# PWU.net
KiCad netlist of a schematic drawn in Altium Designer
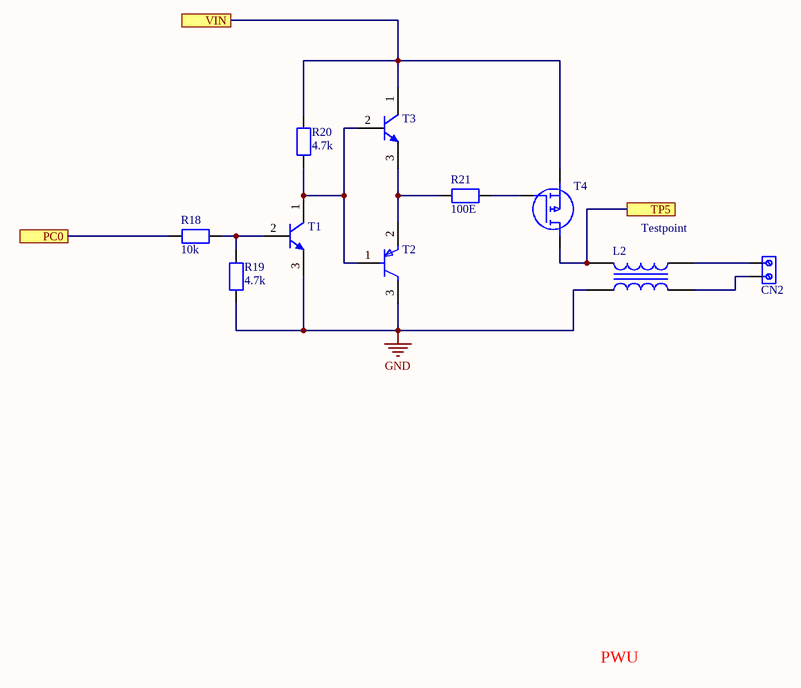
[diagram p0: PWU.SchDoc]

(export (version "E")
  (design (tool "Eeschema 10.0.6"))
  (components
    (comp (ref "CN2")
      (value "connecters 2pins")
      (footprint "conncecto 2 pins")
      (description "printkroonsteen 5,08 mm,")
      (libsource (lib "myOwnLib") (part "pins"))
    )
    (comp (ref "L2")
      (value "CM2545X171R-10")
      (footprint "LIRD-CM2545X171R-10_V")
      (description "Data Line Filter, 2 Function(s), 10A, 4 Pin(s)")
      (fields (field (name "MANUFACTURER") "Laird"))
      (libsource (lib "myOwnLib") (part "CM2545X171R-10"))
    )
    (comp (ref "R18")
      (value "10k")
      (footprint "RES_0805")
      (description "SMD size 0805 Generic.")
      (libsource (lib "myOwnLib") (part "RES_0805"))
    )
    (comp (ref "R19")
      (value "4.7k")
      (footprint "RES_0805")
      (description "SMD size 0805 Generic.")
      (libsource (lib "myOwnLib") (part "RES_0805"))
    )
    (comp (ref "R20")
      (value "4.7k")
      (footprint "RES_0805")
      (description "SMD size 0805 Generic.")
      (libsource (lib "myOwnLib") (part "RES_0805"))
    )
    (comp (ref "R21")
      (value "100E")
      (footprint "RES_0805")
      (description "SMD size 0805 Generic.")
      (libsource (lib "myOwnLib") (part "RES_0805"))
    )
    (comp (ref "T1")
      (value "BC547CG")
      (footprint "ONSC-TO-92-3-29-11")
      (description "Small Signal Bipolar Transistor, 0.1A I(C), 45V V(BR)CEO, 1-Element, NPN, Silicon, TO-92")
      (fields (field (name "MANUFACTURER") "ON Semiconductor"))
      (libsource (lib "myOwnLib") (part "BC547CG"))
    )
    (comp (ref "T2")
      (value "BCV26")
      (footprint "FP-318-IPC_C")
      (description "Small Signal Bipolar Transistor, 1.2A I(C), 30V V(BR)CEO, 1-Element, PNP, Silicon")
      (fields (field (name "MANUFACTURER") "ON Semiconductor / Fairchild"))
      (libsource (lib "myOwnLib") (part "BCV26"))
    )
    (comp (ref "T3")
      (value "BC547CG")
      (footprint "ONSC-TO-92-3-29-11")
      (description "Small Signal Bipolar Transistor, 0.1A I(C), 45V V(BR)CEO, 1-Element, NPN, Silicon, TO-92")
      (fields (field (name "MANUFACTURER") "ON Semiconductor"))
      (libsource (lib "myOwnLib") (part "BC547CG"))
    )
    (comp (ref "T4")
      (value "Mosfet")
      (footprint "TO254P469X1042X1967-3P")
      (description "Mosfet Transistor, IRF9Z34NPBF, generic.")
      (libsource (lib "myOwnLib") (part "Mosfet"))
    )
  )
  (nets
    (net (code "1") (name "/PC0") (class "Default") (node (ref "R18") (pin "1") (pintype "passive")))
    (net (code "2") (name "/TP5") (class "Default")
      (node (ref "L2") (pin "1") (pinfunction "1_1") (pintype "passive"))
      (node (ref "T4") (pin "3") (pinfunction "D_3") (pintype "passive"))
    )
    (net (code "3") (name "/VIN") (class "Default")
      (node (ref "R20") (pin "2") (pintype "passive"))
      (node (ref "T3") (pin "1") (pinfunction "C_1") (pintype "passive"))
      (node (ref "T4") (pin "2") (pinfunction "S_2") (pintype "passive"))
    )
    (net (code "4") (name "GND") (class "Default")
      (node (ref "L2") (pin "2") (pinfunction "2_2") (pintype "passive"))
      (node (ref "R19") (pin "1") (pintype "passive"))
      (node (ref "T1") (pin "3") (pinfunction "E_3") (pintype "passive"))
      (node (ref "T2") (pin "3") (pinfunction "C_3") (pintype "passive"))
    )
    (net (code "5") (name "Net-(CN2-Pad1)") (class "Default")
      (node (ref "CN2") (pin "1") (pinfunction "1_1") (pintype "passive"))
      (node (ref "L2") (pin "4") (pinfunction "4_4") (pintype "passive"))
    )
    (net (code "6") (name "Net-(CN2-Pad2)") (class "Default")
      (node (ref "CN2") (pin "2") (pinfunction "2_2") (pintype "passive"))
      (node (ref "L2") (pin "3") (pinfunction "3_3") (pintype "passive"))
    )
    (net (code "7") (name "Net-(T1-B)") (class "Default")
      (node (ref "R18") (pin "2") (pintype "passive"))
      (node (ref "R19") (pin "2") (pintype "passive"))
      (node (ref "T1") (pin "2") (pinfunction "B_2") (pintype "passive"))
    )
    (net (code "8") (name "Net-(T1-C)") (class "Default")
      (node (ref "R20") (pin "1") (pintype "passive"))
      (node (ref "T1") (pin "1") (pinfunction "C_1") (pintype "passive"))
      (node (ref "T2") (pin "1") (pinfunction "B_1") (pintype "passive"))
      (node (ref "T3") (pin "2") (pinfunction "B_2") (pintype "passive"))
    )
    (net (code "9") (name "Net-(T2-E)") (class "Default")
      (node (ref "R21") (pin "1") (pintype "passive"))
      (node (ref "T2") (pin "2") (pinfunction "E_2") (pintype "passive"))
      (node (ref "T3") (pin "3") (pinfunction "E_3") (pintype "passive"))
    )
    (net (code "10") (name "Net-(T4-G)") (class "Default")
      (node (ref "R21") (pin "2") (pintype "passive"))
      (node (ref "T4") (pin "1") (pinfunction "G_1") (pintype "passive"))
    )
  )
)
